# Sheet_1_2023-09-30.net
KiCad netlist of a schematic drawn in Altium Designer
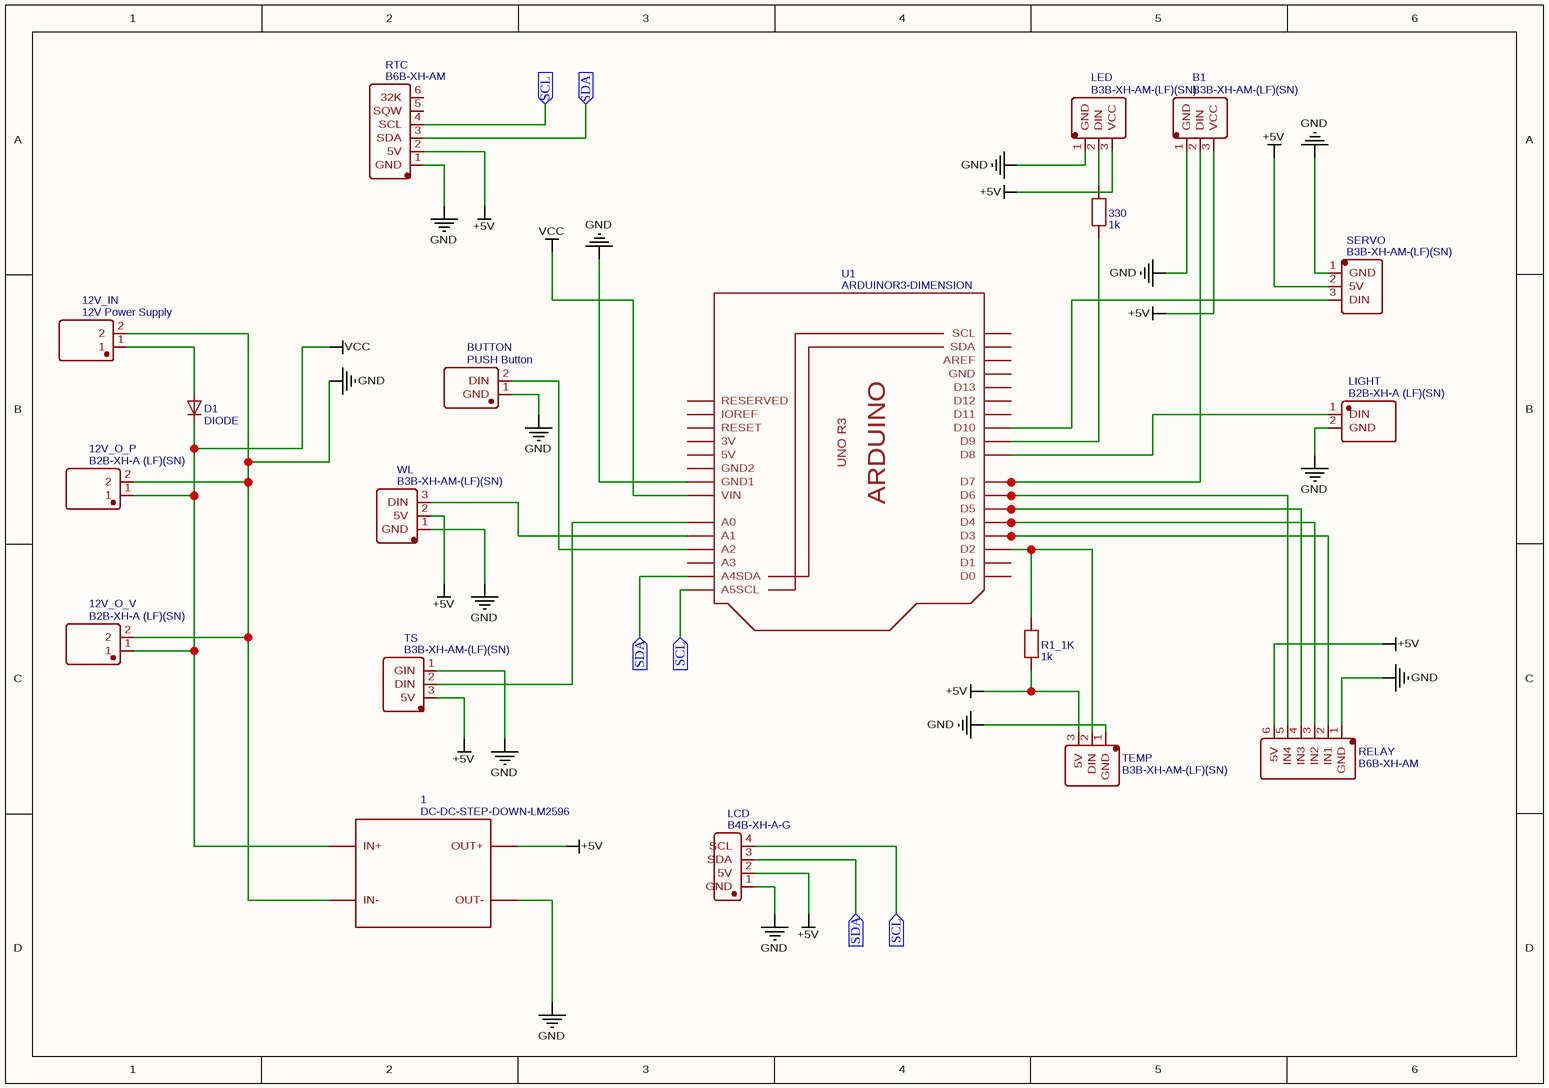
[diagram p0: Sheet_1_2023-09-30.schdoc]

(export (version "E")
  (design (tool "Eeschema 10.0.6"))
  (components
    (comp (ref "1")
      (value "DC-DC-STEP-DOWN-LM2596")
      (fields (field (name "CONTRIBUTOR") "irukaict"))
      (libsource (lib "altium-import") (part "root_0_DC-DC-STEP-DOWN-LM2596_"))
    )
    (comp (ref "12V_IN")
      (value "12V Power Supply")
      (fields
        (field (name "BOM_SUPPLIER PART") "C158012")
        (field (name "BOM_MANUFACTURER PART") "B2B-XH-A(LF)(SN)")
        (field (name "CONTRIBUTOR") "LCSC")
      )
      (libsource (lib "altium-import") (part "root_2_12V Power Supply_"))
    )
    (comp (ref "12V_O_P")
      (value "B2B-XH-A (LF)(SN)")
      (fields
        (field (name "BOM_SUPPLIER PART") "C158012")
        (field (name "BOM_MANUFACTURER PART") "B2B-XH-A(LF)(SN)")
        (field (name "CONTRIBUTOR") "LCSC")
      )
      (libsource (lib "altium-import") (part "root_2_B2B-XH-A (LF)(SN)_"))
    )
    (comp (ref "12V_O_V")
      (value "B2B-XH-A (LF)(SN)")
      (fields
        (field (name "BOM_SUPPLIER PART") "C158012")
        (field (name "BOM_MANUFACTURER PART") "B2B-XH-A(LF)(SN)")
        (field (name "CONTRIBUTOR") "LCSC")
      )
      (libsource (lib "altium-import") (part "root_2_B2B-XH-A (LF)(SN)_"))
    )
    (comp (ref "330")
      (value "1k")
      (fields (field (name "CONTRIBUTOR") "LCEDA_Lib"))
      (libsource (lib "altium-import") (part "root_1_1k_"))
    )
    (comp (ref "B1")
      (value "B3B-XH-AM-(LF)(SN)")
      (fields
        (field (name "BOM_SUPPLIER PART") "C161870")
        (field (name "BOM_MANUFACTURER PART") "B3B-XH-AM(LF)(SN)")
        (field (name "CONTRIBUTOR") "LCSC")
      )
      (libsource (lib "altium-import") (part "root_1_B3B-XH-AM-(LF)(SN)_"))
    )
    (comp (ref "BUTTON")
      (value "PUSH Button")
      (fields
        (field (name "BOM_SUPPLIER PART") "C158012")
        (field (name "BOM_MANUFACTURER PART") "B2B-XH-A(LF)(SN)")
        (field (name "CONTRIBUTOR") "LCSC")
      )
      (libsource (lib "altium-import") (part "root_2_PUSH Button_"))
    )
    (comp (ref "D1")
      (value "DIODE")
      (fields (field (name "CONTRIBUTOR") "Mskaa"))
      (libsource (lib "altium-import") (part "root_3_DIODE_"))
    )
    (comp (ref "LCD")
      (value "B4B-XH-A-G")
      (fields (field (name "BOM_SUPPLIER PART") "C594232") (field (name "CONTRIBUTOR") "LCSC"))
      (libsource (lib "altium-import") (part "root_2_B4B-XH-A-G_"))
    )
    (comp (ref "LED")
      (value "B3B-XH-AM-(LF)(SN)")
      (fields
        (field (name "BOM_SUPPLIER PART") "C161870")
        (field (name "BOM_MANUFACTURER PART") "B3B-XH-AM(LF)(SN)")
        (field (name "CONTRIBUTOR") "LCSC")
      )
      (libsource (lib "altium-import") (part "root_1_B3B-XH-AM-(LF)(SN)_"))
    )
    (comp (ref "LIGHT")
      (value "B2B-XH-A (LF)(SN)")
      (fields
        (field (name "BOM_SUPPLIER PART") "C158012")
        (field (name "BOM_MANUFACTURER PART") "B2B-XH-A(LF)(SN)")
        (field (name "CONTRIBUTOR") "LCSC")
      )
      (libsource (lib "altium-import") (part "root_0_B2B-XH-A (LF)(SN)_"))
    )
    (comp (ref "R1_1K")
      (value "1k")
      (fields (field (name "CONTRIBUTOR") "LCEDA_Lib"))
      (libsource (lib "altium-import") (part "root_1_1k_"))
    )
    (comp (ref "RELAY")
      (value "B6B-XH-AM")
      (fields (field (name "BOM_SUPPLIER PART") "C5306541") (field (name "CONTRIBUTOR") "lcsc"))
      (libsource (lib "altium-import") (part "root_3_B6B-XH-AM_"))
    )
    (comp (ref "RTC")
      (value "B6B-XH-AM")
      (fields (field (name "BOM_SUPPLIER PART") "C5306541") (field (name "CONTRIBUTOR") "lcsc"))
      (libsource (lib "altium-import") (part "root_2_B6B-XH-AM_"))
    )
    (comp (ref "SERVO")
      (value "B3B-XH-AM-(LF)(SN)")
      (fields
        (field (name "BOM_SUPPLIER PART") "C161870")
        (field (name "BOM_MANUFACTURER PART") "B3B-XH-AM(LF)(SN)")
        (field (name "CONTRIBUTOR") "LCSC")
      )
      (libsource (lib "altium-import") (part "root_0_B3B-XH-AM-(LF)(SN)_"))
    )
    (comp (ref "TEMP")
      (value "B3B-XH-AM-(LF)(SN)")
      (fields
        (field (name "BOM_SUPPLIER PART") "C161870")
        (field (name "BOM_MANUFACTURER PART") "B3B-XH-AM(LF)(SN)")
        (field (name "CONTRIBUTOR") "LCSC")
      )
      (libsource (lib "altium-import") (part "root_3_B3B-XH-AM-(LF)(SN)_"))
    )
    (comp (ref "TS")
      (value "B3B-XH-AM-(LF)(SN)")
      (fields
        (field (name "BOM_SUPPLIER PART") "C161870")
        (field (name "BOM_MANUFACTURER PART") "B3B-XH-AM(LF)(SN)")
        (field (name "CONTRIBUTOR") "LCSC")
      )
      (libsource (lib "") (part "root_2_B3B-XH-AM-(LF)(SN)__1"))
    )
    (comp (ref "U1")
      (value "ARDUINOR3-DIMENSION")
      (fields (field (name "CONTRIBUTOR") "Adafruit"))
      (libsource (lib "altium-import") (part "root_3_ARDUINOR3-DIMENSION_"))
    )
    (comp (ref "WL")
      (value "B3B-XH-AM-(LF)(SN)")
      (fields
        (field (name "BOM_SUPPLIER PART") "C161870")
        (field (name "BOM_MANUFACTURER PART") "B3B-XH-AM(LF)(SN)")
        (field (name "CONTRIBUTOR") "LCSC")
      )
      (libsource (lib "altium-import") (part "root_2_B3B-XH-AM-(LF)(SN)_"))
    )
  )
  (nets
    (net (code "1") (name "+5V") (class "Default")
      (node (ref "1") (pin "OUT+") (pinfunction "OUT+_OUT+") (pintype "passive"))
      (node (ref "B1") (pin "3") (pinfunction "VCC_3") (pintype "passive"))
      (node (ref "LCD") (pin "2") (pinfunction "5V_2") (pintype "passive"))
      (node (ref "LED") (pin "3") (pinfunction "VCC_3") (pintype "passive"))
      (node (ref "R1_1K") (pin "1") (pinfunction "1_1") (pintype "passive"))
      (node (ref "RELAY") (pin "6") (pinfunction "5V_6") (pintype "passive"))
      (node (ref "RTC") (pin "2") (pinfunction "5V_2") (pintype "passive"))
      (node (ref "SERVO") (pin "2") (pinfunction "5V_2") (pintype "passive"))
      (node (ref "TEMP") (pin "3") (pinfunction "5V_3") (pintype "passive"))
      (node (ref "TS") (pin "3") (pinfunction "5V_3") (pintype "passive"))
      (node (ref "WL") (pin "2") (pinfunction "5V_2") (pintype "passive"))
    )
    (net (code "2") (name "/SCL") (class "Default")
      (node (ref "LCD") (pin "4") (pinfunction "SCL_4") (pintype "passive"))
      (node (ref "RTC") (pin "4") (pinfunction "SCL_4") (pintype "passive"))
      (node (ref "U1") (pin "A5") (pinfunction "A5SCL_A5") (pintype "passive"))
    )
    (net (code "3") (name "/SDA") (class "Default")
      (node (ref "LCD") (pin "3") (pinfunction "SDA_3") (pintype "passive"))
      (node (ref "RTC") (pin "3") (pinfunction "SDA_3") (pintype "passive"))
      (node (ref "U1") (pin "A4") (pinfunction "A4SDA_A4") (pintype "passive"))
    )
    (net (code "4") (name "GND") (class "Default")
      (node (ref "1") (pin "IN-") (pinfunction "IN-_IN-") (pintype "passive"))
      (node (ref "1") (pin "OUT-") (pinfunction "OUT-_OUT-") (pintype "passive"))
      (node (ref "12V_IN") (pin "2") (pinfunction "2_2") (pintype "passive"))
      (node (ref "12V_O_P") (pin "2") (pinfunction "2_2") (pintype "passive"))
      (node (ref "12V_O_V") (pin "2") (pinfunction "2_2") (pintype "passive"))
      (node (ref "B1") (pin "1") (pinfunction "GND_1") (pintype "passive"))
      (node (ref "BUTTON") (pin "1") (pinfunction "GND_1") (pintype "passive"))
      (node (ref "LCD") (pin "1") (pinfunction "GND_1") (pintype "passive"))
      (node (ref "LED") (pin "1") (pinfunction "GND_1") (pintype "passive"))
      (node (ref "LIGHT") (pin "2") (pinfunction "GND_2") (pintype "passive"))
      (node (ref "RELAY") (pin "1") (pinfunction "GND_1") (pintype "passive"))
      (node (ref "RTC") (pin "1") (pinfunction "GND_1") (pintype "passive"))
      (node (ref "SERVO") (pin "1") (pinfunction "GND_1") (pintype "passive"))
      (node (ref "TEMP") (pin "1") (pinfunction "GND_1") (pintype "passive"))
      (node (ref "TS") (pin "1") (pinfunction "GIN_1") (pintype "passive"))
      (node (ref "U1") (pin "GND1") (pinfunction "GND1_GND1") (pintype "passive"))
      (node (ref "WL") (pin "1") (pinfunction "GND_1") (pintype "passive"))
    )
    (net (code "5") (name "Net-(12V_IN-Pad1)") (class "Default")
      (node (ref "12V_IN") (pin "1") (pinfunction "1_1") (pintype "passive"))
      (node (ref "D1") (pin "A") (pinfunction "A_A") (pintype "passive"))
    )
    (net (code "6") (name "Net-(330-Pad1)") (class "Default")
      (node (ref "330") (pin "1") (pinfunction "1_1") (pintype "passive"))
      (node (ref "U1") (pin "D9") (pinfunction "D9_D9") (pintype "passive"))
    )
    (net (code "7") (name "Net-(B1-DIN)") (class "Default")
      (node (ref "B1") (pin "2") (pinfunction "DIN_2") (pintype "passive"))
      (node (ref "U1") (pin "D7") (pinfunction "D7_D7") (pintype "passive"))
    )
    (net (code "8") (name "Net-(BUTTON-DIN)") (class "Default")
      (node (ref "BUTTON") (pin "2") (pinfunction "DIN_2") (pintype "passive"))
      (node (ref "U1") (pin "A2") (pinfunction "A2_A2") (pintype "passive"))
    )
    (net (code "9") (name "Net-(LED-DIN)") (class "Default")
      (node (ref "330") (pin "2") (pinfunction "2_2") (pintype "passive"))
      (node (ref "LED") (pin "2") (pinfunction "DIN_2") (pintype "passive"))
    )
    (net (code "10") (name "Net-(LIGHT-DIN)") (class "Default")
      (node (ref "LIGHT") (pin "1") (pinfunction "DIN_1") (pintype "passive"))
      (node (ref "U1") (pin "D8") (pinfunction "D8_D8") (pintype "passive"))
    )
    (net (code "11") (name "Net-(RELAY-IN1)") (class "Default")
      (node (ref "RELAY") (pin "2") (pinfunction "IN1_2") (pintype "passive"))
      (node (ref "U1") (pin "D3") (pinfunction "D3_D3") (pintype "passive"))
    )
    (net (code "12") (name "Net-(RELAY-IN2)") (class "Default")
      (node (ref "RELAY") (pin "3") (pinfunction "IN2_3") (pintype "passive"))
      (node (ref "U1") (pin "D4") (pinfunction "D4_D4") (pintype "passive"))
    )
    (net (code "13") (name "Net-(RELAY-IN3)") (class "Default")
      (node (ref "RELAY") (pin "4") (pinfunction "IN3_4") (pintype "passive"))
      (node (ref "U1") (pin "D5") (pinfunction "D5_D5") (pintype "passive"))
    )
    (net (code "14") (name "Net-(RELAY-IN4)") (class "Default")
      (node (ref "RELAY") (pin "5") (pinfunction "IN4_5") (pintype "passive"))
      (node (ref "U1") (pin "D6") (pinfunction "D6_D6") (pintype "passive"))
    )
    (net (code "15") (name "Net-(SERVO-DIN)") (class "Default")
      (node (ref "SERVO") (pin "3") (pinfunction "DIN_3") (pintype "passive"))
      (node (ref "U1") (pin "D10") (pinfunction "D10_D10") (pintype "passive"))
    )
    (net (code "16") (name "Net-(TEMP-DIN)") (class "Default")
      (node (ref "R1_1K") (pin "2") (pinfunction "2_2") (pintype "passive"))
      (node (ref "TEMP") (pin "2") (pinfunction "DIN_2") (pintype "passive"))
      (node (ref "U1") (pin "D2") (pinfunction "D2_D2") (pintype "passive"))
    )
    (net (code "17") (name "Net-(TS-DIN)") (class "Default")
      (node (ref "TS") (pin "2") (pinfunction "DIN_2") (pintype "passive"))
      (node (ref "U1") (pin "A0") (pinfunction "A0_A0") (pintype "passive"))
    )
    (net (code "18") (name "Net-(WL-DIN)") (class "Default")
      (node (ref "U1") (pin "A1") (pinfunction "A1_A1") (pintype "passive"))
      (node (ref "WL") (pin "3") (pinfunction "DIN_3") (pintype "passive"))
    )
    (net (code "19") (name "VCC") (class "Default")
      (node (ref "1") (pin "IN+") (pinfunction "IN+_IN+") (pintype "passive"))
      (node (ref "12V_O_P") (pin "1") (pinfunction "1_1") (pintype "passive"))
      (node (ref "12V_O_V") (pin "1") (pinfunction "1_1") (pintype "passive"))
      (node (ref "D1") (pin "C") (pinfunction "C_C") (pintype "passive"))
      (node (ref "U1") (pin "VIN") (pinfunction "VIN_VIN") (pintype "passive"))
    )
    (net (code "20") (name "unconnected-(RTC-32K-Pad6)") (class "Default")
      (node (ref "RTC") (pin "6") (pinfunction "32K_6") (pintype "passive"))
    )
    (net (code "21") (name "unconnected-(RTC-SQW-Pad5)") (class "Default")
      (node (ref "RTC") (pin "5") (pinfunction "SQW_5") (pintype "passive"))
    )
    (net (code "22") (name "unconnected-(U1-Pad3V)") (class "Default")
      (node (ref "U1") (pin "3V") (pinfunction "3V_3V") (pintype "passive"))
    )
    (net (code "23") (name "unconnected-(U1-Pad5V)") (class "Default")
      (node (ref "U1") (pin "5V") (pinfunction "5V_5V") (pintype "passive"))
    )
    (net (code "24") (name "unconnected-(U1-PadA3)") (class "Default")
      (node (ref "U1") (pin "A3") (pinfunction "A3_A3") (pintype "passive"))
    )
    (net (code "25") (name "unconnected-(U1-PadAREF)") (class "Default")
      (node (ref "U1") (pin "AREF") (pinfunction "AREF_AREF") (pintype "passive"))
    )
    (net (code "26") (name "unconnected-(U1-PadD0)") (class "Default")
      (node (ref "U1") (pin "D0") (pinfunction "D0_D0") (pintype "passive"))
    )
    (net (code "27") (name "unconnected-(U1-PadD1)") (class "Default")
      (node (ref "U1") (pin "D1") (pinfunction "D1_D1") (pintype "passive"))
    )
    (net (code "28") (name "unconnected-(U1-PadD11)") (class "Default")
      (node (ref "U1") (pin "D11") (pinfunction "D11_D11") (pintype "passive"))
    )
    (net (code "29") (name "unconnected-(U1-PadD12)") (class "Default")
      (node (ref "U1") (pin "D12") (pinfunction "D12_D12") (pintype "passive"))
    )
    (net (code "30") (name "unconnected-(U1-PadD13)") (class "Default")
      (node (ref "U1") (pin "D13") (pinfunction "D13_D13") (pintype "passive"))
    )
    (net (code "31") (name "unconnected-(U1-PadGND)") (class "Default")
      (node (ref "U1") (pin "GND") (pinfunction "GND_GND") (pintype "passive"))
    )
    (net (code "32") (name "unconnected-(U1-PadGND2)") (class "Default")
      (node (ref "U1") (pin "GND2") (pinfunction "GND2_GND2") (pintype "passive"))
    )
    (net (code "33") (name "unconnected-(U1-PadIOREF)") (class "Default")
      (node (ref "U1") (pin "IOREF") (pinfunction "IOREF_IOREF") (pintype "passive"))
    )
    (net (code "34") (name "unconnected-(U1-PadRESERVED)") (class "Default")
      (node (ref "U1") (pin "RESERVED") (pinfunction "RESERVED_RESERVED") (pintype "passive"))
    )
    (net (code "35") (name "unconnected-(U1-PadRESET)") (class "Default")
      (node (ref "U1") (pin "RESET") (pinfunction "RESET_RESET") (pintype "passive"))
    )
    (net (code "36") (name "unconnected-(U1-PadSCL)") (class "Default")
      (node (ref "U1") (pin "SCL") (pinfunction "SCL_SCL") (pintype "passive"))
    )
    (net (code "37") (name "unconnected-(U1-PadSDA)") (class "Default")
      (node (ref "U1") (pin "SDA") (pinfunction "SDA_SDA") (pintype "passive"))
    )
  )
)
